# PCB_USA-A_HUB_Schematics_EasyEDA_File.net
KiCad netlist of a schematic drawn in EasyEDA
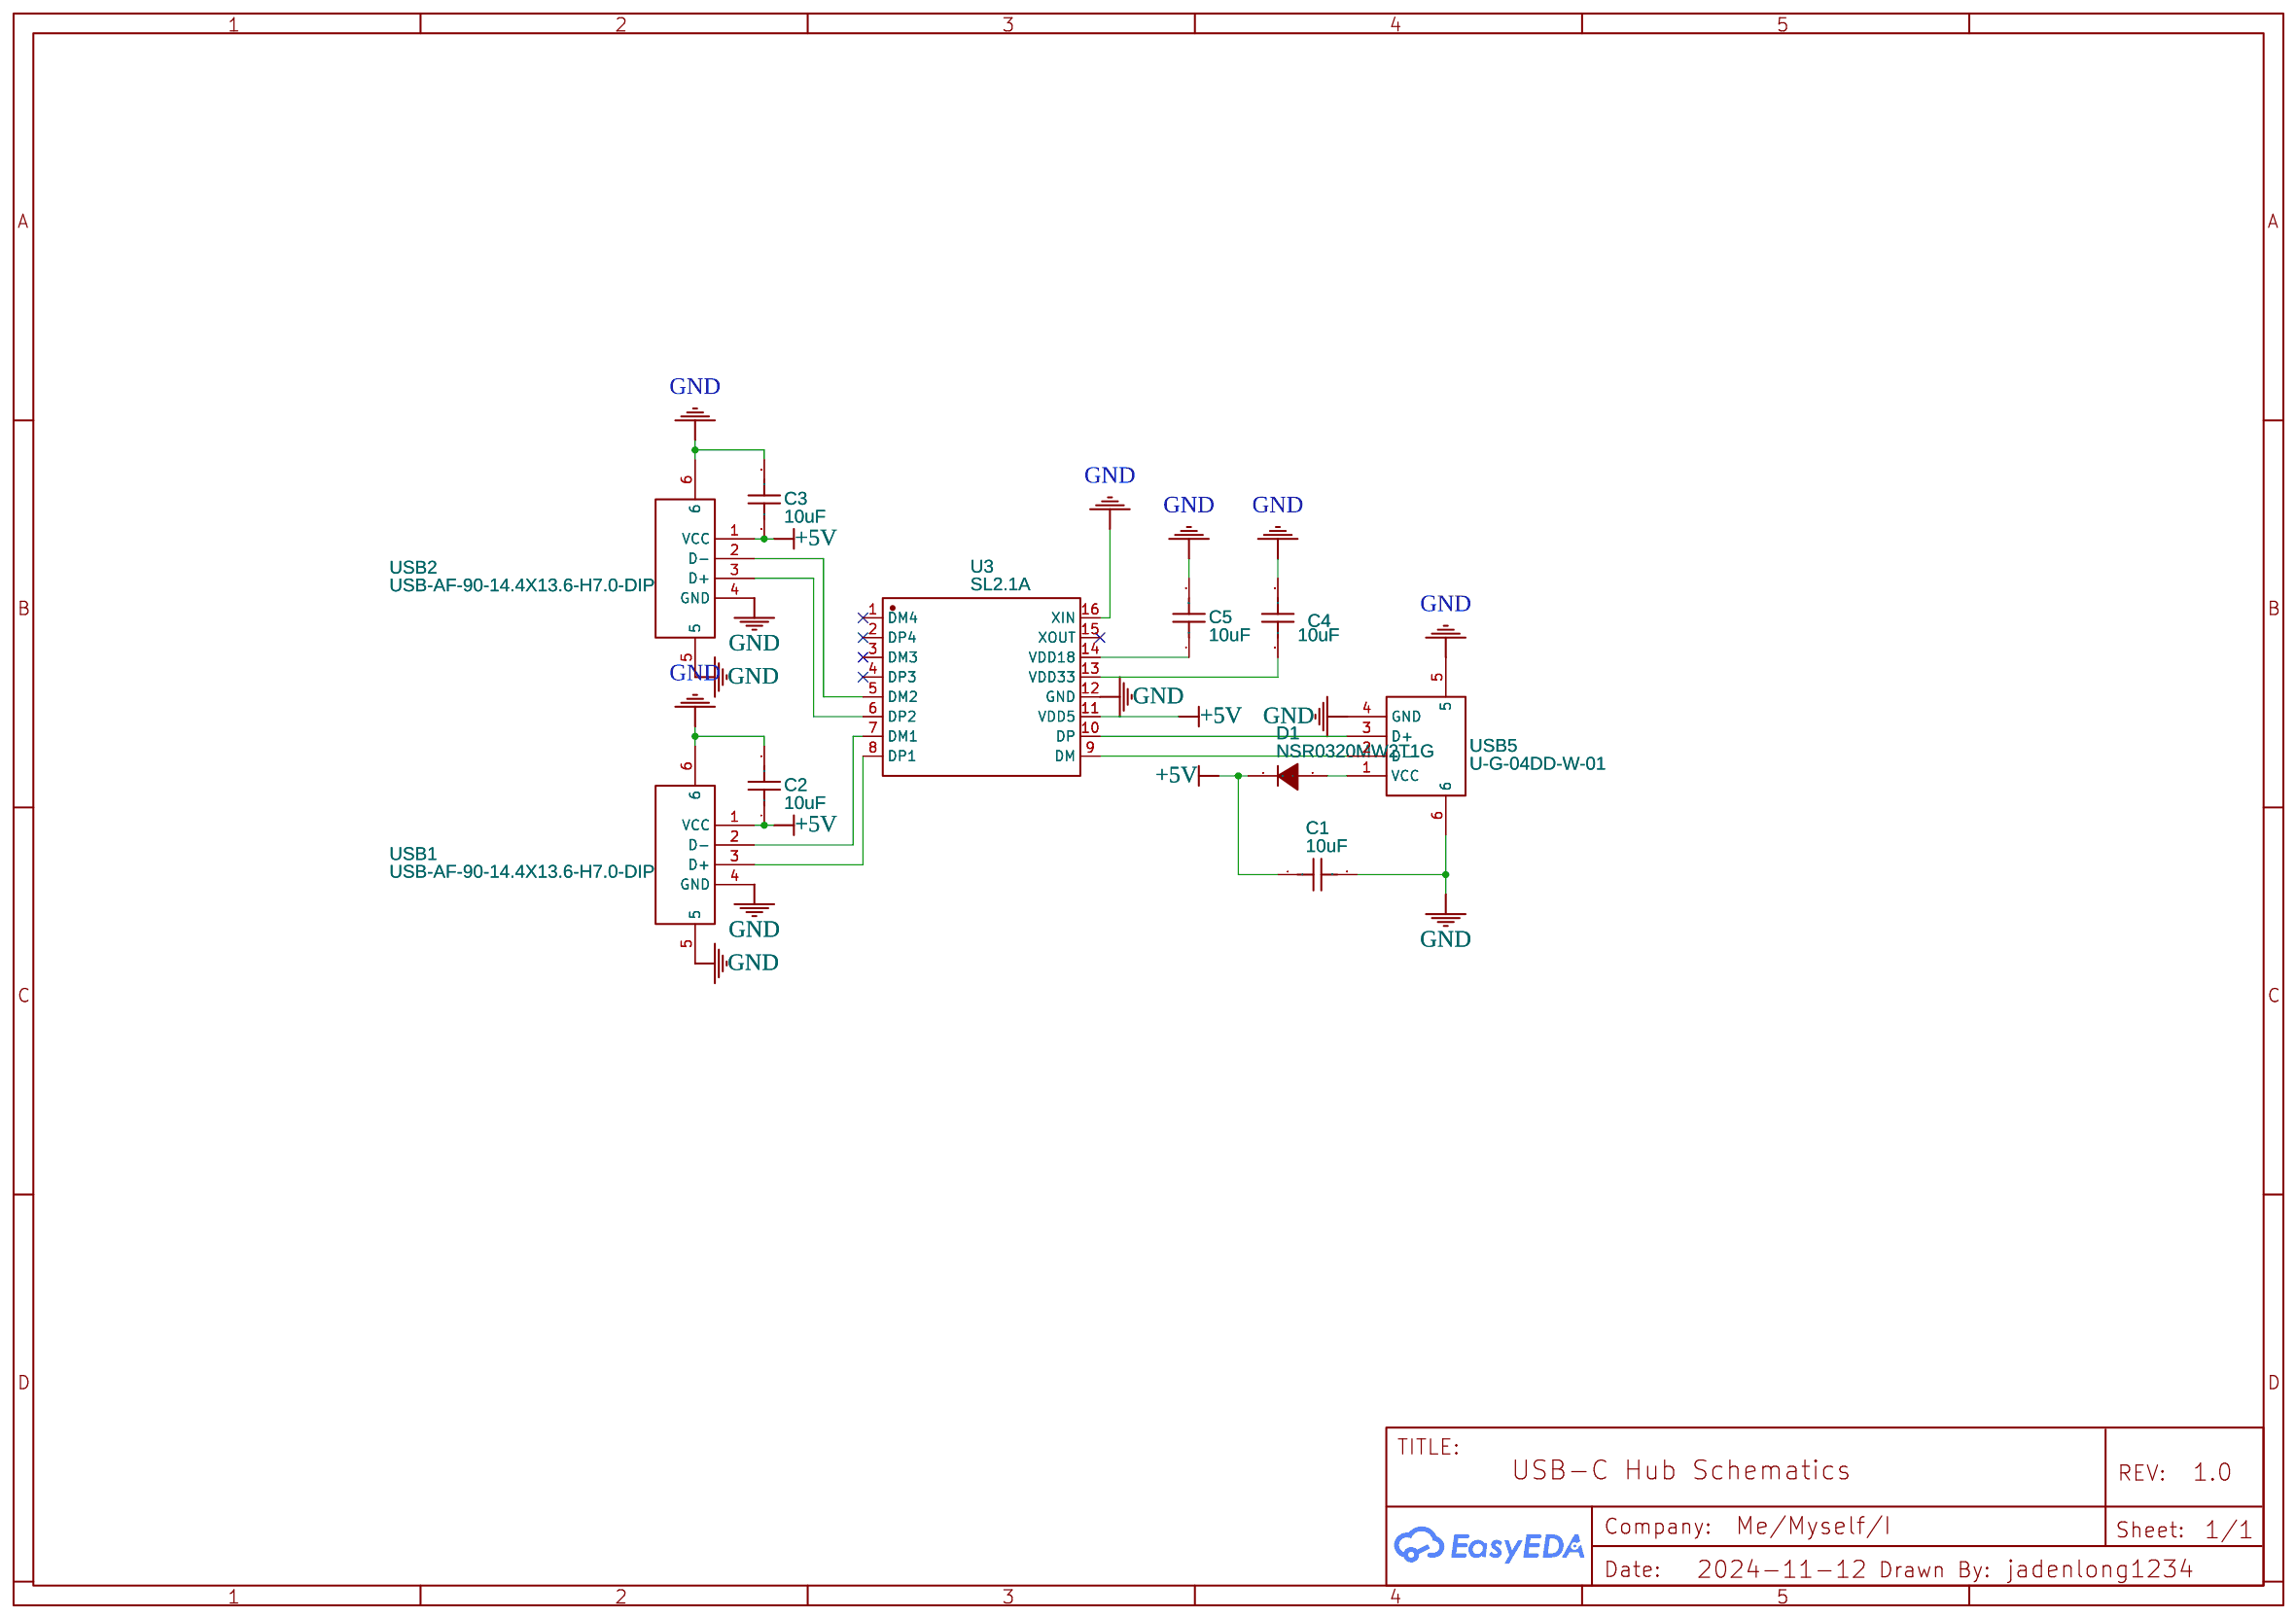
[diagram p0: schematic sheet]

(export (version "E")
  (design (tool "Eeschema 10.0.6"))
  (components
    (comp (ref "C1")
      (value "10uF")
      (fields
        (field (name "Manufacturer Part") "CL10A106KP8NNNC")
        (field (name "Manufacturer") "SAMSUNG(三星)")
      )
      (libsource (lib "") (part "CL10A106KP8NNNC_1"))
    )
    (comp (ref "C2")
      (value "10uF")
      (fields
        (field (name "Manufacturer Part") "CL10A106KP8NNNC")
        (field (name "Manufacturer") "SAMSUNG(三星)")
      )
      (libsource (lib "") (part "CL10A106KP8NNNC"))
    )
    (comp (ref "C3")
      (value "10uF")
      (fields
        (field (name "Manufacturer Part") "CL10A106KP8NNNC")
        (field (name "Manufacturer") "SAMSUNG(三星)")
      )
      (libsource (lib "") (part "CL10A106KP8NNNC"))
    )
    (comp (ref "C4")
      (value "10uF")
      (fields
        (field (name "Manufacturer Part") "CL10A106KP8NNNC")
        (field (name "Manufacturer") "SAMSUNG(三星)")
      )
      (libsource (lib "") (part "CL10A106KP8NNNC"))
    )
    (comp (ref "C5")
      (value "10uF")
      (fields
        (field (name "Manufacturer Part") "CL10A106KP8NNNC")
        (field (name "Manufacturer") "SAMSUNG(三星)")
      )
      (libsource (lib "") (part "CL10A106KP8NNNC"))
    )
    (comp (ref "D1")
      (value "NSR0320MW2T1G")
      (fields (field (name "Manufacturer") "onsemi(安森美)"))
      (libsource (lib "") (part "NSR0320MW2T1G"))
    )
    (comp (ref "U3")
      (value "SL2.1A")
      (fields (field (name "Manufacturer") "CoreChips(和芯润德)"))
      (libsource (lib "") (part "SL2.1A"))
    )
    (comp (ref "USB1")
      (value "USB-AF-90-14.4X13.6-H7.0-DIP")
      (fields (field (name "Manufacturer Part") "903-131A1011D10100") (field (name "Manufacturer") "精拓金"))
      (libsource (lib "") (part "USB-AF-90-14.4X13.6-H7.0-DIP"))
    )
    (comp (ref "USB2")
      (value "USB-AF-90-14.4X13.6-H7.0-DIP")
      (fields (field (name "Manufacturer Part") "903-131A1011D10100") (field (name "Manufacturer") "精拓金"))
      (libsource (lib "") (part "USB-AF-90-14.4X13.6-H7.0-DIP"))
    )
    (comp (ref "USB5")
      (value "U-G-04DD-W-01")
      (fields (field (name "Manufacturer Part") "U-G-O4DD-W-1") (field (name "Manufacturer") "韩国韩荣"))
      (libsource (lib "") (part "U-G-04DD-W-01"))
    )
  )
  (nets
    (net (code "1") (name "+5V") (class "Default")
      (node (ref "C1") (pin "1") (pinfunction "1_1") (pintype "unspecified"))
      (node (ref "C2") (pin "1") (pinfunction "1_1") (pintype "unspecified"))
      (node (ref "C3") (pin "1") (pinfunction "1_1") (pintype "unspecified"))
      (node (ref "D1") (pin "1") (pinfunction "C_1") (pintype "unspecified"))
      (node (ref "U3") (pin "11") (pinfunction "VDD5_11") (pintype "unspecified"))
      (node (ref "USB1") (pin "1") (pinfunction "VCC_1") (pintype "unspecified"))
      (node (ref "USB2") (pin "1") (pinfunction "VCC_1") (pintype "unspecified"))
    )
    (net (code "2") (name "GND") (class "Default")
      (node (ref "C1") (pin "2") (pinfunction "2_2") (pintype "unspecified"))
      (node (ref "C2") (pin "2") (pinfunction "2_2") (pintype "unspecified"))
      (node (ref "C3") (pin "2") (pinfunction "2_2") (pintype "unspecified"))
      (node (ref "C4") (pin "2") (pinfunction "2_2") (pintype "unspecified"))
      (node (ref "C5") (pin "2") (pinfunction "2_2") (pintype "unspecified"))
      (node (ref "U3") (pin "12") (pinfunction "GND_12") (pintype "unspecified"))
      (node (ref "U3") (pin "16") (pinfunction "XIN_16") (pintype "unspecified"))
      (node (ref "USB1") (pin "4") (pinfunction "GND_4") (pintype "unspecified"))
      (node (ref "USB1") (pin "5") (pinfunction "5_5") (pintype "unspecified"))
      (node (ref "USB1") (pin "6") (pinfunction "6_6") (pintype "unspecified"))
      (node (ref "USB2") (pin "4") (pinfunction "GND_4") (pintype "unspecified"))
      (node (ref "USB2") (pin "5") (pinfunction "5_5") (pintype "unspecified"))
      (node (ref "USB2") (pin "6") (pinfunction "6_6") (pintype "unspecified"))
      (node (ref "USB5") (pin "4") (pinfunction "GND_4") (pintype "unspecified"))
      (node (ref "USB5") (pin "5") (pinfunction "5_5") (pintype "unspecified"))
      (node (ref "USB5") (pin "6") (pinfunction "6_6") (pintype "unspecified"))
    )
    (net (code "3") (name "Net-(D1-A)") (class "Default")
      (node (ref "D1") (pin "2") (pinfunction "A_2") (pintype "unspecified"))
      (node (ref "USB5") (pin "1") (pinfunction "VCC_1") (pintype "unspecified"))
    )
    (net (code "4") (name "Net-(U3-DM)") (class "Default")
      (node (ref "U3") (pin "9") (pinfunction "DM_9") (pintype "unspecified"))
      (node (ref "USB5") (pin "2") (pinfunction "D-_2") (pintype "unspecified"))
    )
    (net (code "5") (name "Net-(U3-DM1)") (class "Default")
      (node (ref "U3") (pin "7") (pinfunction "DM1_7") (pintype "unspecified"))
      (node (ref "USB1") (pin "2") (pinfunction "D-_2") (pintype "unspecified"))
    )
    (net (code "6") (name "Net-(U3-DM2)") (class "Default")
      (node (ref "U3") (pin "5") (pinfunction "DM2_5") (pintype "unspecified"))
      (node (ref "USB2") (pin "2") (pinfunction "D-_2") (pintype "unspecified"))
    )
    (net (code "7") (name "Net-(U3-DP)") (class "Default")
      (node (ref "U3") (pin "10") (pinfunction "DP_10") (pintype "unspecified"))
      (node (ref "USB5") (pin "3") (pinfunction "D+_3") (pintype "unspecified"))
    )
    (net (code "8") (name "Net-(U3-DP1)") (class "Default")
      (node (ref "U3") (pin "8") (pinfunction "DP1_8") (pintype "unspecified"))
      (node (ref "USB1") (pin "3") (pinfunction "D+_3") (pintype "unspecified"))
    )
    (net (code "9") (name "Net-(U3-DP2)") (class "Default")
      (node (ref "U3") (pin "6") (pinfunction "DP2_6") (pintype "unspecified"))
      (node (ref "USB2") (pin "3") (pinfunction "D+_3") (pintype "unspecified"))
    )
    (net (code "10") (name "Net-(U3-VDD18)") (class "Default")
      (node (ref "C5") (pin "1") (pinfunction "1_1") (pintype "unspecified"))
      (node (ref "U3") (pin "14") (pinfunction "VDD18_14") (pintype "unspecified"))
    )
    (net (code "11") (name "Net-(U3-VDD33)") (class "Default")
      (node (ref "C4") (pin "1") (pinfunction "1_1") (pintype "unspecified"))
      (node (ref "U3") (pin "13") (pinfunction "VDD33_13") (pintype "unspecified"))
    )
    (net (code "12") (name "unconnected-(U3-DM3-Pad3)") (class "Default")
      (node (ref "U3") (pin "3") (pinfunction "DM3_3") (pintype "unspecified+no_connect"))
    )
    (net (code "13") (name "unconnected-(U3-DM4-Pad1)") (class "Default")
      (node (ref "U3") (pin "1") (pinfunction "DM4_1") (pintype "unspecified+no_connect"))
    )
    (net (code "14") (name "unconnected-(U3-DP3-Pad4)") (class "Default")
      (node (ref "U3") (pin "4") (pinfunction "DP3_4") (pintype "unspecified+no_connect"))
    )
    (net (code "15") (name "unconnected-(U3-DP4-Pad2)") (class "Default")
      (node (ref "U3") (pin "2") (pinfunction "DP4_2") (pintype "unspecified+no_connect"))
    )
    (net (code "16") (name "unconnected-(U3-XOUT-Pad15)") (class "Default")
      (node (ref "U3") (pin "15") (pinfunction "XOUT_15") (pintype "unspecified+no_connect"))
    )
  )
)
